# preamp.net
KiCad netlist of a schematic drawn in EAGLE
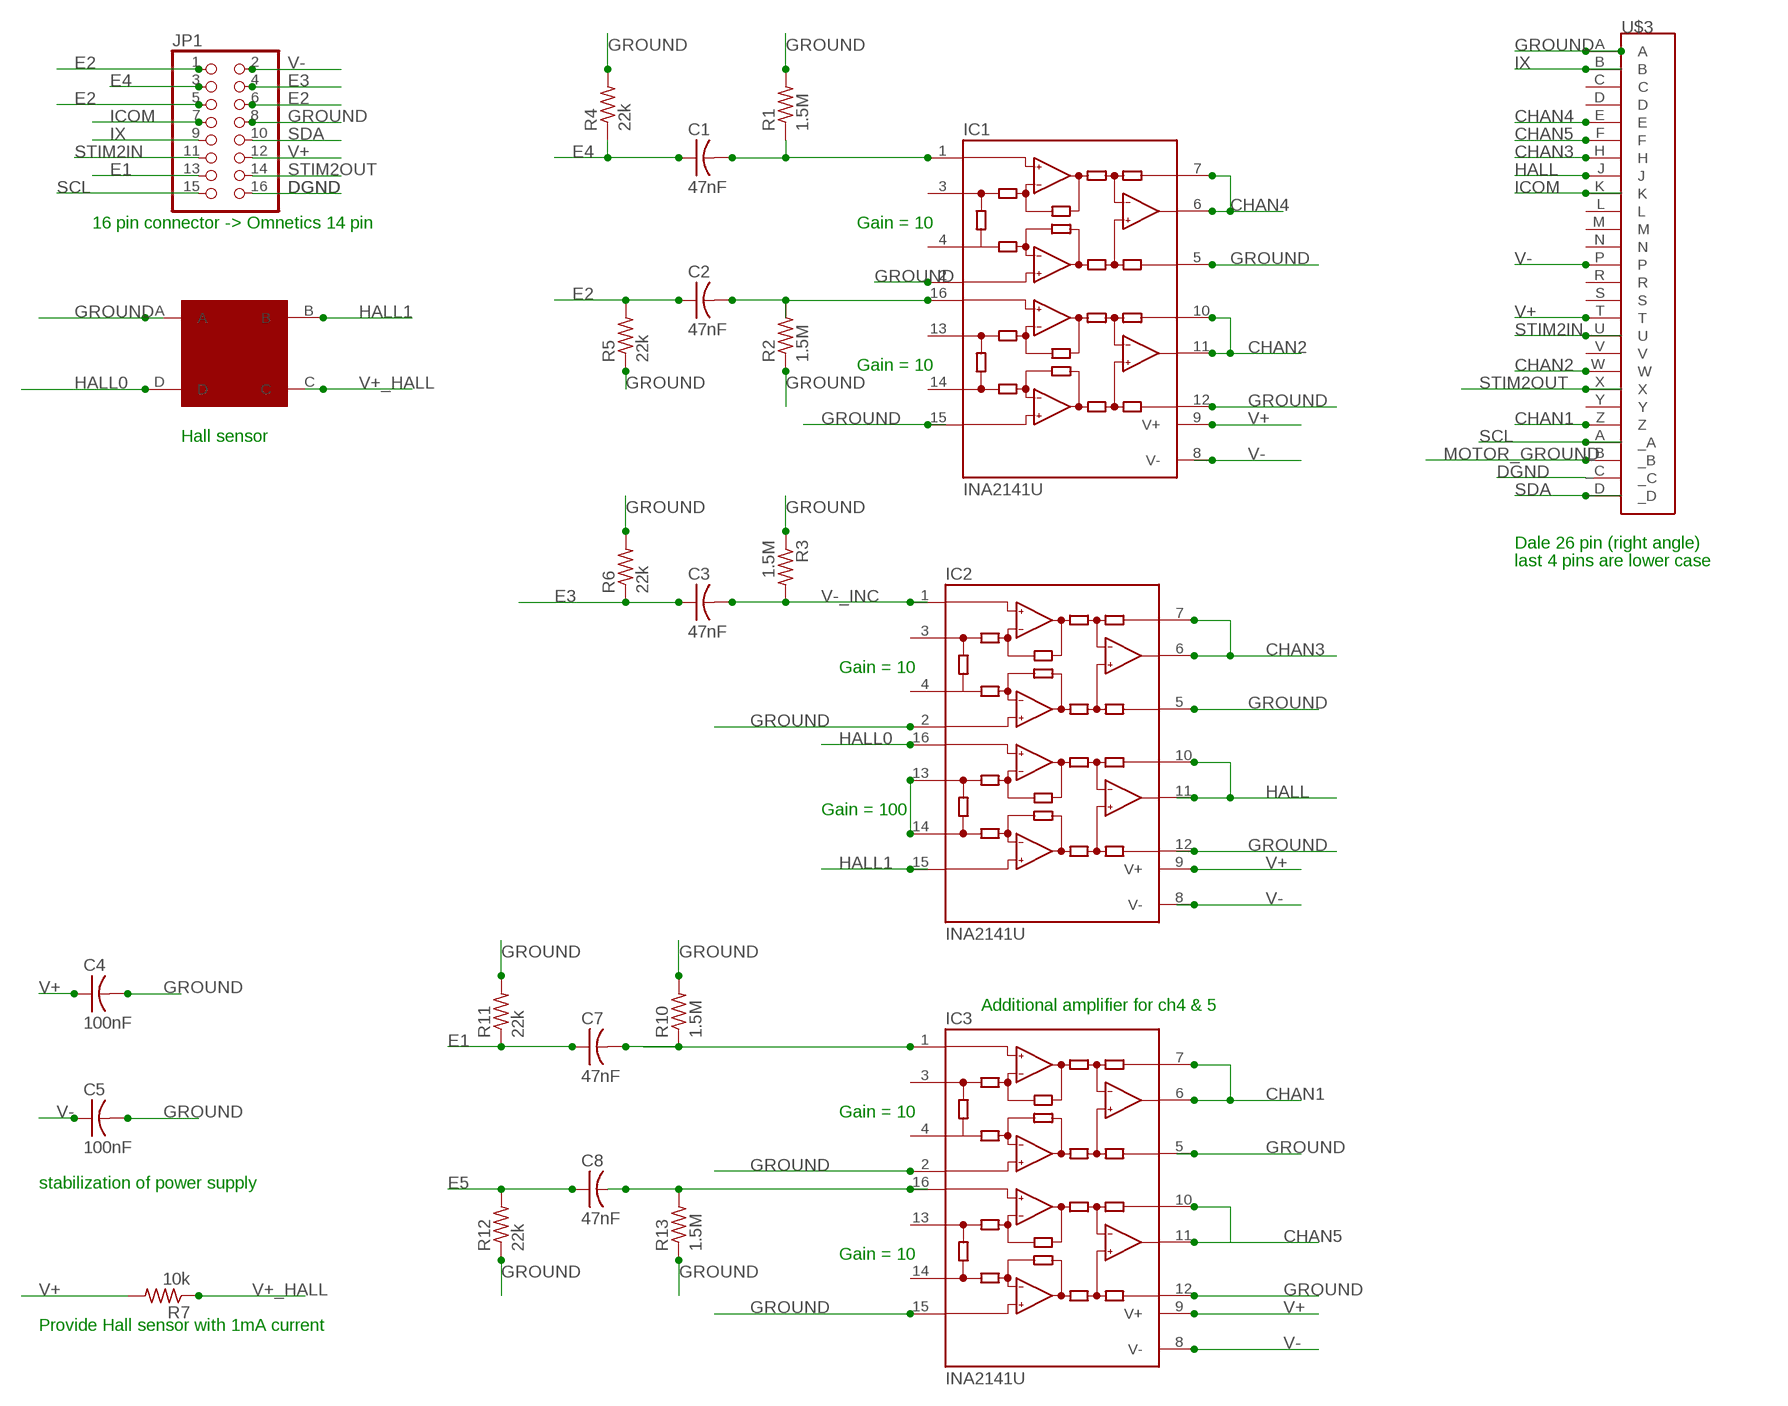
[diagram p0: schematic, sheet 1]

(export (version "E")
  (design (tool "Eeschema 10.0.6"))
  (components
    (comp (ref "C1")
      (value "47nF")
      (footprint "eagle-import:R0805ELM")
      (libsource (lib "eagle-import") (part "C0805ELM"))
    )
    (comp (ref "C2")
      (value "47nF")
      (footprint "eagle-import:R0805ELM")
      (libsource (lib "eagle-import") (part "C0805ELM"))
    )
    (comp (ref "C3")
      (value "47nF")
      (footprint "eagle-import:R0805ELM")
      (libsource (lib "eagle-import") (part "C0805ELM"))
    )
    (comp (ref "C4")
      (value "100nF")
      (footprint "eagle-import:R0805ELM")
      (libsource (lib "eagle-import") (part "C0805ELM"))
    )
    (comp (ref "C5")
      (value "100nF")
      (footprint "eagle-import:R0805ELM")
      (libsource (lib "eagle-import") (part "C0805ELM"))
    )
    (comp (ref "C7")
      (value "47nF")
      (footprint "eagle-import:R0805ELM")
      (libsource (lib "eagle-import") (part "C0805ELM"))
    )
    (comp (ref "C8")
      (value "47nF")
      (footprint "eagle-import:R0805ELM")
      (libsource (lib "eagle-import") (part "C0805ELM"))
    )
    (comp (ref "IC1")
      (value "INA2141U")
      (footprint "eagle-import:SO16-1")
      (fields (field (name "MF") "TEXAS INSTRUMENT CONNECTORS"))
      (libsource (lib "eagle-import") (part "INA2141U"))
    )
    (comp (ref "IC2")
      (value "INA2141U")
      (footprint "eagle-import:SO16-1")
      (fields (field (name "MF") "TEXAS INSTRUMENT CONNECTORS"))
      (libsource (lib "eagle-import") (part "INA2141U"))
    )
    (comp (ref "IC3")
      (value "INA2141U")
      (footprint "eagle-import:SO16-1")
      (fields (field (name "MF") "TEXAS INSTRUMENT CONNECTORS"))
      (libsource (lib "eagle-import") (part "INA2141U"))
    )
    (comp (ref "JP1")
      (value "PINHD-2X8")
      (footprint "eagle-import:2X08")
      (libsource (lib "eagle-import") (part "PINHD-2X8"))
    )
    (comp (ref "R1")
      (value "1.5M")
      (footprint "eagle-import:R0805ELM")
      (libsource (lib "eagle-import") (part "R0805ELM"))
    )
    (comp (ref "R2")
      (value "1.5M")
      (footprint "eagle-import:R0805ELM")
      (libsource (lib "eagle-import") (part "R0805ELM"))
    )
    (comp (ref "R3")
      (value "1.5M")
      (footprint "eagle-import:R0805ELM")
      (libsource (lib "eagle-import") (part "R0805ELM"))
    )
    (comp (ref "R4")
      (value "22k")
      (footprint "eagle-import:R0805ELM")
      (libsource (lib "eagle-import") (part "R0805ELM"))
    )
    (comp (ref "R5")
      (value "22k")
      (footprint "eagle-import:R0805ELM")
      (libsource (lib "eagle-import") (part "R0805ELM"))
    )
    (comp (ref "R6")
      (value "22k")
      (footprint "eagle-import:R0805ELM")
      (libsource (lib "eagle-import") (part "R0805ELM"))
    )
    (comp (ref "R7")
      (value "10k")
      (footprint "eagle-import:R0805ELM")
      (libsource (lib "eagle-import") (part "R0805ELM"))
    )
    (comp (ref "R10")
      (value "1.5M")
      (footprint "eagle-import:R0805ELM")
      (libsource (lib "eagle-import") (part "R0805ELM"))
    )
    (comp (ref "R11")
      (value "22k")
      (footprint "eagle-import:R0805ELM")
      (libsource (lib "eagle-import") (part "R0805ELM"))
    )
    (comp (ref "R12")
      (value "22k")
      (footprint "eagle-import:R0805ELM")
      (libsource (lib "eagle-import") (part "R0805ELM"))
    )
    (comp (ref "R13")
      (value "1.5M")
      (footprint "eagle-import:R0805ELM")
      (libsource (lib "eagle-import") (part "R0805ELM"))
    )
    (comp (ref "U$2")
      (value "HALL")
      (footprint "eagle-import:HALL_ON_SIDE")
      (libsource (lib "eagle-import") (part "HALL_ON_SIDE"))
    )
    (comp (ref "U$3")
      (value "MMD1P22G-26-M101")
      (footprint "eagle-import:MMD1P22G-26-M101")
      (libsource (lib "eagle-import") (part "MMD1P22G-26-M101"))
    )
  )
  (nets
    (net (code "1") (name "/CHAN1") (class "Default")
      (node (ref "IC3") (pin "6") (pinfunction "VOA_6") (pintype "output"))
      (node (ref "IC3") (pin "7") (pinfunction "SENSEA_7") (pintype "input"))
      (node (ref "U$3") (pin "Z") (pinfunction "Z_Z") (pintype "bidirectional"))
    )
    (net (code "2") (name "/CHAN2") (class "Default")
      (node (ref "IC1") (pin "10") (pinfunction "SENSEB_10") (pintype "input"))
      (node (ref "IC1") (pin "11") (pinfunction "VOB_11") (pintype "output"))
      (node (ref "U$3") (pin "W") (pinfunction "W_W") (pintype "bidirectional"))
    )
    (net (code "3") (name "/CHAN3") (class "Default")
      (node (ref "IC2") (pin "6") (pinfunction "VOA_6") (pintype "output"))
      (node (ref "IC2") (pin "7") (pinfunction "SENSEA_7") (pintype "input"))
      (node (ref "U$3") (pin "H") (pinfunction "H_H") (pintype "bidirectional"))
    )
    (net (code "4") (name "/CHAN4") (class "Default")
      (node (ref "IC1") (pin "6") (pinfunction "VOA_6") (pintype "output"))
      (node (ref "IC1") (pin "7") (pinfunction "SENSEA_7") (pintype "input"))
      (node (ref "U$3") (pin "E") (pinfunction "E_E") (pintype "bidirectional"))
    )
    (net (code "5") (name "/CHAN5") (class "Default")
      (node (ref "IC3") (pin "10") (pinfunction "SENSEB_10") (pintype "input"))
      (node (ref "IC3") (pin "11") (pinfunction "VOB_11") (pintype "output"))
      (node (ref "U$3") (pin "F") (pinfunction "F_F") (pintype "bidirectional"))
    )
    (net (code "6") (name "/DGND") (class "Default")
      (node (ref "JP1") (pin "16") (pinfunction "16_16") (pintype "passive"))
      (node (ref "U$3") (pin "_C") (pinfunction "_C__C") (pintype "bidirectional"))
    )
    (net (code "7") (name "/E1") (class "Default")
      (node (ref "C7") (pin "1") (pinfunction "1_1") (pintype "passive"))
      (node (ref "JP1") (pin "13") (pinfunction "13_13") (pintype "passive"))
      (node (ref "R11") (pin "1") (pinfunction "1_1") (pintype "passive"))
    )
    (net (code "8") (name "/E2") (class "Default")
      (node (ref "C2") (pin "1") (pinfunction "1_1") (pintype "passive"))
      (node (ref "JP1") (pin "1") (pinfunction "1_1") (pintype "passive"))
      (node (ref "JP1") (pin "5") (pinfunction "5_5") (pintype "passive"))
      (node (ref "JP1") (pin "6") (pinfunction "6_6") (pintype "passive"))
      (node (ref "R5") (pin "2") (pinfunction "2_2") (pintype "passive"))
    )
    (net (code "9") (name "/E3") (class "Default")
      (node (ref "C3") (pin "1") (pinfunction "1_1") (pintype "passive"))
      (node (ref "JP1") (pin "4") (pinfunction "4_4") (pintype "passive"))
      (node (ref "R6") (pin "1") (pinfunction "1_1") (pintype "passive"))
    )
    (net (code "10") (name "/E4") (class "Default")
      (node (ref "C1") (pin "1") (pinfunction "1_1") (pintype "passive"))
      (node (ref "JP1") (pin "3") (pinfunction "3_3") (pintype "passive"))
      (node (ref "R4") (pin "1") (pinfunction "1_1") (pintype "passive"))
    )
    (net (code "11") (name "/E5") (class "Default")
      (node (ref "C8") (pin "1") (pinfunction "1_1") (pintype "passive"))
      (node (ref "R12") (pin "2") (pinfunction "2_2") (pintype "passive"))
    )
    (net (code "12") (name "/GROUND") (class "Default")
      (node (ref "C4") (pin "2") (pinfunction "2_2") (pintype "passive"))
      (node (ref "C5") (pin "2") (pinfunction "2_2") (pintype "passive"))
      (node (ref "IC1") (pin "12") (pinfunction "REFB_12") (pintype "input"))
      (node (ref "IC1") (pin "15") (pinfunction "INB+_15") (pintype "input"))
      (node (ref "IC1") (pin "2") (pinfunction "INA+_2") (pintype "input"))
      (node (ref "IC1") (pin "5") (pinfunction "REFA_5") (pintype "input"))
      (node (ref "IC2") (pin "12") (pinfunction "REFB_12") (pintype "input"))
      (node (ref "IC2") (pin "2") (pinfunction "INA+_2") (pintype "input"))
      (node (ref "IC2") (pin "5") (pinfunction "REFA_5") (pintype "input"))
      (node (ref "IC3") (pin "12") (pinfunction "REFB_12") (pintype "input"))
      (node (ref "IC3") (pin "15") (pinfunction "INB+_15") (pintype "input"))
      (node (ref "IC3") (pin "2") (pinfunction "INA+_2") (pintype "input"))
      (node (ref "IC3") (pin "5") (pinfunction "REFA_5") (pintype "input"))
      (node (ref "JP1") (pin "8") (pinfunction "8_8") (pintype "passive"))
      (node (ref "R1") (pin "2") (pinfunction "2_2") (pintype "passive"))
      (node (ref "R10") (pin "2") (pinfunction "2_2") (pintype "passive"))
      (node (ref "R11") (pin "2") (pinfunction "2_2") (pintype "passive"))
      (node (ref "R12") (pin "1") (pinfunction "1_1") (pintype "passive"))
      (node (ref "R13") (pin "1") (pinfunction "1_1") (pintype "passive"))
      (node (ref "R2") (pin "1") (pinfunction "1_1") (pintype "passive"))
      (node (ref "R3") (pin "1") (pinfunction "1_1") (pintype "passive"))
      (node (ref "R4") (pin "2") (pinfunction "2_2") (pintype "passive"))
      (node (ref "R5") (pin "1") (pinfunction "1_1") (pintype "passive"))
      (node (ref "R6") (pin "2") (pinfunction "2_2") (pintype "passive"))
      (node (ref "U$2") (pin "A") (pinfunction "A_A") (pintype "bidirectional"))
      (node (ref "U$3") (pin "A") (pinfunction "A_A") (pintype "bidirectional"))
    )
    (net (code "13") (name "/HALL") (class "Default")
      (node (ref "IC2") (pin "10") (pinfunction "SENSEB_10") (pintype "input"))
      (node (ref "IC2") (pin "11") (pinfunction "VOB_11") (pintype "output"))
      (node (ref "U$3") (pin "J") (pinfunction "J_J") (pintype "bidirectional"))
    )
    (net (code "14") (name "/HALL0") (class "Default")
      (node (ref "IC2") (pin "16") (pinfunction "INB-_16") (pintype "input"))
      (node (ref "U$2") (pin "D") (pinfunction "D_D") (pintype "bidirectional"))
    )
    (net (code "15") (name "/HALL1") (class "Default")
      (node (ref "IC2") (pin "15") (pinfunction "INB+_15") (pintype "input"))
      (node (ref "U$2") (pin "B") (pinfunction "B_B") (pintype "bidirectional"))
    )
    (net (code "16") (name "/ICOM") (class "Default")
      (node (ref "JP1") (pin "7") (pinfunction "7_7") (pintype "passive"))
      (node (ref "U$3") (pin "K") (pinfunction "K_K") (pintype "bidirectional"))
    )
    (net (code "17") (name "/IX") (class "Default")
      (node (ref "JP1") (pin "9") (pinfunction "9_9") (pintype "passive"))
      (node (ref "U$3") (pin "B") (pinfunction "B_B") (pintype "bidirectional"))
    )
    (net (code "18") (name "/MOTOR_GROUND") (class "Default")
      (node (ref "U$3") (pin "_B") (pinfunction "_B__B") (pintype "bidirectional"))
    )
    (net (code "19") (name "/SCL") (class "Default")
      (node (ref "JP1") (pin "15") (pinfunction "15_15") (pintype "passive"))
      (node (ref "U$3") (pin "_A") (pinfunction "_A__A") (pintype "bidirectional"))
    )
    (net (code "20") (name "/SDA") (class "Default")
      (node (ref "JP1") (pin "10") (pinfunction "10_10") (pintype "passive"))
      (node (ref "U$3") (pin "_D") (pinfunction "_D__D") (pintype "bidirectional"))
    )
    (net (code "21") (name "/STIM2IN") (class "Default")
      (node (ref "JP1") (pin "11") (pinfunction "11_11") (pintype "passive"))
      (node (ref "U$3") (pin "U") (pinfunction "U_U") (pintype "bidirectional"))
    )
    (net (code "22") (name "/STIM2OUT") (class "Default")
      (node (ref "JP1") (pin "14") (pinfunction "14_14") (pintype "passive"))
      (node (ref "U$3") (pin "X") (pinfunction "X_X") (pintype "bidirectional"))
    )
    (net (code "23") (name "/V+") (class "Default")
      (node (ref "C4") (pin "1") (pinfunction "1_1") (pintype "passive"))
      (node (ref "IC1") (pin "9") (pinfunction "V+_9") (pintype "power_in"))
      (node (ref "IC2") (pin "9") (pinfunction "V+_9") (pintype "power_in"))
      (node (ref "IC3") (pin "9") (pinfunction "V+_9") (pintype "power_in"))
      (node (ref "JP1") (pin "12") (pinfunction "12_12") (pintype "passive"))
      (node (ref "R7") (pin "2") (pinfunction "2_2") (pintype "passive"))
      (node (ref "U$3") (pin "T") (pinfunction "T_T") (pintype "bidirectional"))
    )
    (net (code "24") (name "/V+_HALL") (class "Default")
      (node (ref "R7") (pin "1") (pinfunction "1_1") (pintype "passive"))
      (node (ref "U$2") (pin "C") (pinfunction "C_C") (pintype "bidirectional"))
    )
    (net (code "25") (name "/V-") (class "Default")
      (node (ref "C5") (pin "1") (pinfunction "1_1") (pintype "passive"))
      (node (ref "IC1") (pin "8") (pinfunction "V-_8") (pintype "power_in"))
      (node (ref "IC2") (pin "8") (pinfunction "V-_8") (pintype "power_in"))
      (node (ref "IC3") (pin "8") (pinfunction "V-_8") (pintype "power_in"))
      (node (ref "JP1") (pin "2") (pinfunction "2_2") (pintype "passive"))
      (node (ref "U$3") (pin "P") (pinfunction "P_P") (pintype "bidirectional"))
    )
    (net (code "26") (name "/V-_INC") (class "Default")
      (node (ref "C3") (pin "2") (pinfunction "2_2") (pintype "passive"))
      (node (ref "IC2") (pin "1") (pinfunction "INA-_1") (pintype "input"))
      (node (ref "R3") (pin "2") (pinfunction "2_2") (pintype "passive"))
    )
    (net (code "27") (name "Net-(IC1-INA-)") (class "Default")
      (node (ref "C1") (pin "2") (pinfunction "2_2") (pintype "passive"))
      (node (ref "IC1") (pin "1") (pinfunction "INA-_1") (pintype "input"))
      (node (ref "R1") (pin "1") (pinfunction "1_1") (pintype "passive"))
    )
    (net (code "28") (name "Net-(IC1-INB-)") (class "Default")
      (node (ref "C2") (pin "2") (pinfunction "2_2") (pintype "passive"))
      (node (ref "IC1") (pin "16") (pinfunction "INB-_16") (pintype "input"))
      (node (ref "R2") (pin "2") (pinfunction "2_2") (pintype "passive"))
    )
    (net (code "29") (name "Net-(IC2-JB-Pad13)") (class "Default")
      (node (ref "IC2") (pin "13") (pinfunction "JB_13") (pintype "passive"))
      (node (ref "IC2") (pin "14") (pinfunction "JB_14") (pintype "passive"))
    )
    (net (code "30") (name "Net-(IC3-INA-)") (class "Default")
      (node (ref "C7") (pin "2") (pinfunction "2_2") (pintype "passive"))
      (node (ref "IC3") (pin "1") (pinfunction "INA-_1") (pintype "input"))
      (node (ref "R10") (pin "1") (pinfunction "1_1") (pintype "passive"))
    )
    (net (code "31") (name "Net-(IC3-INB-)") (class "Default")
      (node (ref "C8") (pin "2") (pinfunction "2_2") (pintype "passive"))
      (node (ref "IC3") (pin "16") (pinfunction "INB-_16") (pintype "input"))
      (node (ref "R13") (pin "2") (pinfunction "2_2") (pintype "passive"))
    )
    (net (code "32") (name "unconnected-(IC1-JA-Pad3)") (class "Default")
      (node (ref "IC1") (pin "3") (pinfunction "JA_3") (pintype "passive"))
    )
    (net (code "33") (name "unconnected-(IC1-JA-Pad4)") (class "Default")
      (node (ref "IC1") (pin "4") (pinfunction "JA_4") (pintype "passive"))
    )
    (net (code "34") (name "unconnected-(IC1-JB-Pad13)") (class "Default")
      (node (ref "IC1") (pin "13") (pinfunction "JB_13") (pintype "passive"))
    )
    (net (code "35") (name "unconnected-(IC1-JB-Pad14)") (class "Default")
      (node (ref "IC1") (pin "14") (pinfunction "JB_14") (pintype "passive"))
    )
    (net (code "36") (name "unconnected-(IC2-JA-Pad3)") (class "Default")
      (node (ref "IC2") (pin "3") (pinfunction "JA_3") (pintype "passive"))
    )
    (net (code "37") (name "unconnected-(IC2-JA-Pad4)") (class "Default")
      (node (ref "IC2") (pin "4") (pinfunction "JA_4") (pintype "passive"))
    )
    (net (code "38") (name "unconnected-(IC3-JA-Pad3)") (class "Default")
      (node (ref "IC3") (pin "3") (pinfunction "JA_3") (pintype "passive"))
    )
    (net (code "39") (name "unconnected-(IC3-JA-Pad4)") (class "Default")
      (node (ref "IC3") (pin "4") (pinfunction "JA_4") (pintype "passive"))
    )
    (net (code "40") (name "unconnected-(IC3-JB-Pad13)") (class "Default")
      (node (ref "IC3") (pin "13") (pinfunction "JB_13") (pintype "passive"))
    )
    (net (code "41") (name "unconnected-(IC3-JB-Pad14)") (class "Default")
      (node (ref "IC3") (pin "14") (pinfunction "JB_14") (pintype "passive"))
    )
    (net (code "42") (name "unconnected-(U$3-PadC)") (class "Default")
      (node (ref "U$3") (pin "C") (pinfunction "C_C") (pintype "bidirectional"))
    )
    (net (code "43") (name "unconnected-(U$3-PadD)") (class "Default")
      (node (ref "U$3") (pin "D") (pinfunction "D_D") (pintype "bidirectional"))
    )
    (net (code "44") (name "unconnected-(U$3-PadL)") (class "Default")
      (node (ref "U$3") (pin "L") (pinfunction "L_L") (pintype "bidirectional"))
    )
    (net (code "45") (name "unconnected-(U$3-PadM)") (class "Default")
      (node (ref "U$3") (pin "M") (pinfunction "M_M") (pintype "bidirectional"))
    )
    (net (code "46") (name "unconnected-(U$3-PadN)") (class "Default")
      (node (ref "U$3") (pin "N") (pinfunction "N_N") (pintype "bidirectional"))
    )
    (net (code "47") (name "unconnected-(U$3-PadR)") (class "Default")
      (node (ref "U$3") (pin "R") (pinfunction "R_R") (pintype "bidirectional"))
    )
    (net (code "48") (name "unconnected-(U$3-PadS)") (class "Default")
      (node (ref "U$3") (pin "S") (pinfunction "S_S") (pintype "bidirectional"))
    )
    (net (code "49") (name "unconnected-(U$3-PadV)") (class "Default")
      (node (ref "U$3") (pin "V") (pinfunction "V_V") (pintype "bidirectional"))
    )
    (net (code "50") (name "unconnected-(U$3-PadY)") (class "Default")
      (node (ref "U$3") (pin "Y") (pinfunction "Y_Y") (pintype "bidirectional"))
    )
  )
)
